# 2x_--_gegensprechanlage.net
KiCad netlist of a schematic drawn in EAGLE
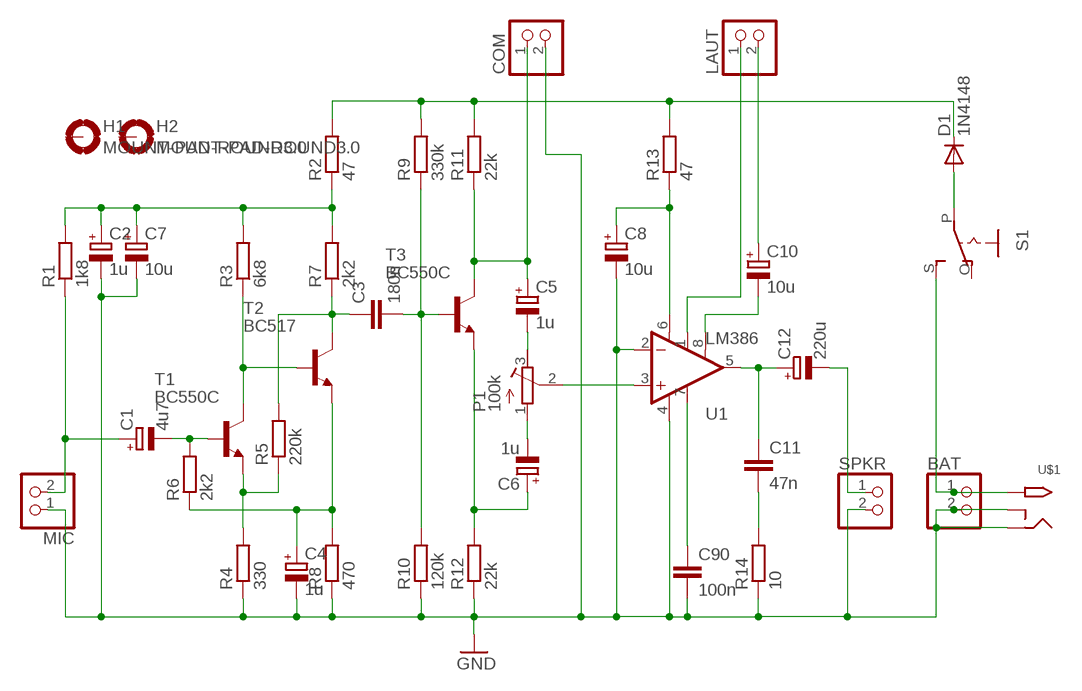
[diagram p0: schematic, sheet 1]

(export (version "E")
  (design (tool "Eeschema 10.0.6"))
  (components
    (comp (ref "BAT")
      (value "PINHD-1X2")
      (footprint "eagle-import:1X02")
      (libsource (lib "eagle-import") (part "PINHD-1X2"))
    )
    (comp (ref "C1")
      (value "4u7")
      (footprint "eagle-import:E2,5-6")
      (libsource (lib "eagle-import") (part "CPOL-EUE2.5-6"))
    )
    (comp (ref "C2")
      (value "1u")
      (footprint "eagle-import:E2,5-6")
      (libsource (lib "eagle-import") (part "CPOL-EUE2.5-6"))
    )
    (comp (ref "C3")
      (value "180n")
      (footprint "eagle-import:C025-025X050")
      (libsource (lib "eagle-import") (part "C-EU025-025X050"))
    )
    (comp (ref "C4")
      (value "1u")
      (footprint "eagle-import:E2,5-6")
      (libsource (lib "eagle-import") (part "CPOL-EUE2.5-6"))
    )
    (comp (ref "C5")
      (value "1u")
      (footprint "eagle-import:E2,5-6")
      (libsource (lib "eagle-import") (part "CPOL-EUE2.5-6"))
    )
    (comp (ref "C6")
      (value "1u")
      (footprint "eagle-import:E2,5-6")
      (libsource (lib "eagle-import") (part "CPOL-EUE2.5-6"))
    )
    (comp (ref "C7")
      (value "10u")
      (footprint "eagle-import:E2,5-6")
      (libsource (lib "eagle-import") (part "CPOL-EUE2.5-6"))
    )
    (comp (ref "C8")
      (value "10u")
      (footprint "eagle-import:E2,5-6")
      (libsource (lib "eagle-import") (part "CPOL-EUE2.5-6"))
    )
    (comp (ref "C10")
      (value "10u")
      (footprint "eagle-import:E2,5-6")
      (libsource (lib "eagle-import") (part "CPOL-EUE2.5-6"))
    )
    (comp (ref "C11")
      (value "47n")
      (footprint "eagle-import:C025-025X050")
      (libsource (lib "eagle-import") (part "C-EU025-025X050"))
    )
    (comp (ref "C12")
      (value "220u")
      (footprint "eagle-import:E2,5-6")
      (libsource (lib "eagle-import") (part "CPOL-EUE2.5-6"))
    )
    (comp (ref "C90")
      (value "100n")
      (footprint "eagle-import:C025-025X050")
      (libsource (lib "eagle-import") (part "C-EU025-025X050"))
    )
    (comp (ref "COM")
      (value "PINHD-1X2")
      (footprint "eagle-import:1X02")
      (libsource (lib "eagle-import") (part "PINHD-1X2"))
    )
    (comp (ref "D1")
      (value "1N4148")
      (footprint "eagle-import:D-7.5")
      (libsource (lib "eagle-import") (part "DIODE-D-7.5"))
    )
    (comp (ref "H1")
      (value "MOUNT-PAD-ROUND3.0")
      (footprint "eagle-import:3,0-PAD")
      (libsource (lib "eagle-import") (part "MOUNT-PAD-ROUND3.0"))
    )
    (comp (ref "H2")
      (value "MOUNT-PAD-ROUND3.0")
      (footprint "eagle-import:3,0-PAD")
      (libsource (lib "eagle-import") (part "MOUNT-PAD-ROUND3.0"))
    )
    (comp (ref "LAUT")
      (value "PINHD-1X2")
      (footprint "eagle-import:1X02")
      (libsource (lib "eagle-import") (part "PINHD-1X2"))
    )
    (comp (ref "MIC")
      (value "PINHD-1X2")
      (footprint "eagle-import:1X02")
      (libsource (lib "eagle-import") (part "PINHD-1X2"))
    )
    (comp (ref "P1")
      (value "100k")
      (footprint "eagle-import:RTRIM64P")
      (libsource (lib "eagle-import") (part "R-TRIMM64P"))
    )
    (comp (ref "R1")
      (value "1k8")
      (footprint "eagle-import:0204_7")
      (libsource (lib "eagle-import") (part "R-EU_0204/7"))
    )
    (comp (ref "R2")
      (value "47")
      (footprint "eagle-import:0204_7")
      (libsource (lib "eagle-import") (part "R-EU_0204/7"))
    )
    (comp (ref "R3")
      (value "6k8")
      (footprint "eagle-import:0204_7")
      (libsource (lib "eagle-import") (part "R-EU_0204/7"))
    )
    (comp (ref "R4")
      (value "330")
      (footprint "eagle-import:0204_7")
      (libsource (lib "eagle-import") (part "R-EU_0204/7"))
    )
    (comp (ref "R5")
      (value "220k")
      (footprint "eagle-import:0204_7")
      (libsource (lib "eagle-import") (part "R-EU_0204/7"))
    )
    (comp (ref "R6")
      (value "2k2")
      (footprint "eagle-import:0204_7")
      (libsource (lib "eagle-import") (part "R-EU_0204/7"))
    )
    (comp (ref "R7")
      (value "2k2")
      (footprint "eagle-import:0204_7")
      (libsource (lib "eagle-import") (part "R-EU_0204/7"))
    )
    (comp (ref "R8")
      (value "470")
      (footprint "eagle-import:0204_7")
      (libsource (lib "eagle-import") (part "R-EU_0204/7"))
    )
    (comp (ref "R9")
      (value "330k")
      (footprint "eagle-import:0204_7")
      (libsource (lib "eagle-import") (part "R-EU_0204/7"))
    )
    (comp (ref "R10")
      (value "120k")
      (footprint "eagle-import:0204_7")
      (libsource (lib "eagle-import") (part "R-EU_0204/7"))
    )
    (comp (ref "R11")
      (value "22k")
      (footprint "eagle-import:0204_7")
      (libsource (lib "eagle-import") (part "R-EU_0204/7"))
    )
    (comp (ref "R12")
      (value "22k")
      (footprint "eagle-import:0204_7")
      (libsource (lib "eagle-import") (part "R-EU_0204/7"))
    )
    (comp (ref "R13")
      (value "47")
      (footprint "eagle-import:0204_7")
      (libsource (lib "eagle-import") (part "R-EU_0204/7"))
    )
    (comp (ref "R14")
      (value "10")
      (footprint "eagle-import:0204_7")
      (libsource (lib "eagle-import") (part "R-EU_0204/7"))
    )
    (comp (ref "S1")
      (value "EG1218S")
      (footprint "eagle-import:EG1218")
      (libsource (lib "eagle-import") (part "EG1218S"))
    )
    (comp (ref "SPKR")
      (value "PINHD-1X2")
      (footprint "eagle-import:1X02")
      (libsource (lib "eagle-import") (part "PINHD-1X2"))
    )
    (comp (ref "T1")
      (value "BC550C")
      (footprint "eagle-import:TO92-CBE")
      (libsource (lib "eagle-import") (part "-NPN-TO92-CBEBC550"))
    )
    (comp (ref "T2")
      (value "BC517")
      (footprint "eagle-import:TO92-CBE")
      (libsource (lib "eagle-import") (part "-NPN-TO92-CBEBC550"))
    )
    (comp (ref "T3")
      (value "BC550C")
      (footprint "eagle-import:TO92-CBE")
      (libsource (lib "eagle-import") (part "-NPN-TO92-CBEBC550"))
    )
    (comp (ref "U$1")
      (value "2.1MMJACKTHM")
      (footprint "eagle-import:PJ-102A")
      (libsource (lib "eagle-import") (part "2.1MMJACKTHM"))
    )
    (comp (ref "U1")
      (value "LM386")
      (footprint "eagle-import:DIP08")
      (libsource (lib "eagle-import") (part "LM386"))
    )
  )
  (nets
    (net (code "1") (name "GND") (class "Default")
      (node (ref "BAT") (pin "2") (pinfunction "2_2") (pintype "passive"))
      (node (ref "C2") (pin "-") (pinfunction "-_-") (pintype "passive"))
      (node (ref "C4") (pin "-") (pinfunction "-_-") (pintype "passive"))
      (node (ref "C7") (pin "-") (pinfunction "-_-") (pintype "passive"))
      (node (ref "C8") (pin "-") (pinfunction "-_-") (pintype "passive"))
      (node (ref "C90") (pin "2") (pinfunction "2_2") (pintype "passive"))
      (node (ref "COM") (pin "2") (pinfunction "2_2") (pintype "passive"))
      (node (ref "MIC") (pin "1") (pinfunction "1_1") (pintype "passive"))
      (node (ref "R10") (pin "1") (pinfunction "1_1") (pintype "passive"))
      (node (ref "R12") (pin "1") (pinfunction "1_1") (pintype "passive"))
      (node (ref "R14") (pin "1") (pinfunction "1_1") (pintype "passive"))
      (node (ref "R4") (pin "1") (pinfunction "1_1") (pintype "passive"))
      (node (ref "R8") (pin "1") (pinfunction "1_1") (pintype "passive"))
      (node (ref "SPKR") (pin "2") (pinfunction "2_2") (pintype "passive"))
      (node (ref "U$1") (pin "RING") (pinfunction "RING_RING") (pintype "bidirectional"))
      (node (ref "U$1") (pin "RING_SW") (pinfunction "RING_SW_RING_SW") (pintype "bidirectional"))
      (node (ref "U1") (pin "2") (pinfunction "-IN_2") (pintype "input"))
      (node (ref "U1") (pin "4") (pinfunction "V-_4") (pintype "power_in"))
    )
    (net (code "2") (name "Net-(BAT-Pad1)") (class "Default")
      (node (ref "BAT") (pin "1") (pinfunction "1_1") (pintype "passive"))
      (node (ref "S1") (pin "S") (pinfunction "S_S") (pintype "passive"))
      (node (ref "U$1") (pin "TIP") (pinfunction "TIP_TIP") (pintype "bidirectional"))
    )
    (net (code "3") (name "Net-(C1-Pad+)") (class "Default")
      (node (ref "C1") (pin "+") (pinfunction "+_+") (pintype "passive"))
      (node (ref "MIC") (pin "2") (pinfunction "2_2") (pintype "passive"))
      (node (ref "R1") (pin "1") (pinfunction "1_1") (pintype "passive"))
    )
    (net (code "4") (name "Net-(C1-Pad-)") (class "Default")
      (node (ref "C1") (pin "-") (pinfunction "-_-") (pintype "passive"))
      (node (ref "R6") (pin "2") (pinfunction "2_2") (pintype "passive"))
      (node (ref "T1") (pin "B") (pinfunction "B_B") (pintype "passive"))
    )
    (net (code "5") (name "Net-(C2-Pad+)") (class "Default")
      (node (ref "C2") (pin "+") (pinfunction "+_+") (pintype "passive"))
      (node (ref "C7") (pin "+") (pinfunction "+_+") (pintype "passive"))
      (node (ref "R1") (pin "2") (pinfunction "2_2") (pintype "passive"))
      (node (ref "R2") (pin "1") (pinfunction "1_1") (pintype "passive"))
      (node (ref "R3") (pin "2") (pinfunction "2_2") (pintype "passive"))
      (node (ref "R7") (pin "2") (pinfunction "2_2") (pintype "passive"))
    )
    (net (code "6") (name "Net-(C3-Pad1)") (class "Default")
      (node (ref "C3") (pin "1") (pinfunction "1_1") (pintype "passive"))
      (node (ref "R5") (pin "2") (pinfunction "2_2") (pintype "passive"))
      (node (ref "R7") (pin "1") (pinfunction "1_1") (pintype "passive"))
      (node (ref "T2") (pin "C") (pinfunction "C_C") (pintype "passive"))
    )
    (net (code "7") (name "Net-(C3-Pad2)") (class "Default")
      (node (ref "C3") (pin "2") (pinfunction "2_2") (pintype "passive"))
      (node (ref "R10") (pin "2") (pinfunction "2_2") (pintype "passive"))
      (node (ref "R9") (pin "1") (pinfunction "1_1") (pintype "passive"))
      (node (ref "T3") (pin "B") (pinfunction "B_B") (pintype "passive"))
    )
    (net (code "8") (name "Net-(C4-Pad+)") (class "Default")
      (node (ref "C4") (pin "+") (pinfunction "+_+") (pintype "passive"))
      (node (ref "R6") (pin "1") (pinfunction "1_1") (pintype "passive"))
      (node (ref "R8") (pin "2") (pinfunction "2_2") (pintype "passive"))
      (node (ref "T2") (pin "E") (pinfunction "E_E") (pintype "passive"))
    )
    (net (code "9") (name "Net-(C5-Pad+)") (class "Default")
      (node (ref "C5") (pin "+") (pinfunction "+_+") (pintype "passive"))
      (node (ref "COM") (pin "1") (pinfunction "1_1") (pintype "passive"))
      (node (ref "R11") (pin "1") (pinfunction "1_1") (pintype "passive"))
      (node (ref "T3") (pin "C") (pinfunction "C_C") (pintype "passive"))
    )
    (net (code "10") (name "Net-(C6-Pad+)") (class "Default")
      (node (ref "C6") (pin "+") (pinfunction "+_+") (pintype "passive"))
      (node (ref "R12") (pin "2") (pinfunction "2_2") (pintype "passive"))
      (node (ref "T3") (pin "E") (pinfunction "E_E") (pintype "passive"))
    )
    (net (code "11") (name "Net-(C10-Pad+)") (class "Default")
      (node (ref "C10") (pin "+") (pinfunction "+_+") (pintype "passive"))
      (node (ref "LAUT") (pin "2") (pinfunction "2_2") (pintype "passive"))
    )
    (net (code "12") (name "Net-(C10-Pad-)") (class "Default")
      (node (ref "C10") (pin "-") (pinfunction "-_-") (pintype "passive"))
      (node (ref "U1") (pin "8") (pinfunction "GAIN_8") (pintype "bidirectional"))
    )
    (net (code "13") (name "Net-(C11-Pad2)") (class "Default")
      (node (ref "C11") (pin "2") (pinfunction "2_2") (pintype "passive"))
      (node (ref "R14") (pin "2") (pinfunction "2_2") (pintype "passive"))
    )
    (net (code "14") (name "Net-(C12-Pad-)") (class "Default")
      (node (ref "C12") (pin "-") (pinfunction "-_-") (pintype "passive"))
      (node (ref "SPKR") (pin "1") (pinfunction "1_1") (pintype "passive"))
    )
    (net (code "15") (name "Net-(D1-PadA)") (class "Default")
      (node (ref "D1") (pin "A") (pinfunction "A_A") (pintype "passive"))
      (node (ref "S1") (pin "P") (pinfunction "P_P") (pintype "passive"))
    )
    (net (code "16") (name "Net-(D1-PadC)") (class "Default")
      (node (ref "D1") (pin "C") (pinfunction "C_C") (pintype "passive"))
      (node (ref "R11") (pin "2") (pinfunction "2_2") (pintype "passive"))
      (node (ref "R13") (pin "2") (pinfunction "2_2") (pintype "passive"))
      (node (ref "R2") (pin "2") (pinfunction "2_2") (pintype "passive"))
      (node (ref "R9") (pin "2") (pinfunction "2_2") (pintype "passive"))
    )
    (net (code "17") (name "Net-(LAUT-Pad1)") (class "Default")
      (node (ref "LAUT") (pin "1") (pinfunction "1_1") (pintype "passive"))
      (node (ref "U1") (pin "1") (pinfunction "GAIN_1") (pintype "bidirectional"))
    )
    (net (code "18") (name "Net-(P1-A)") (class "Default")
      (node (ref "C6") (pin "-") (pinfunction "-_-") (pintype "passive"))
      (node (ref "P1") (pin "1") (pinfunction "A_1") (pintype "passive"))
    )
    (net (code "19") (name "Net-(P1-E)") (class "Default")
      (node (ref "C5") (pin "-") (pinfunction "-_-") (pintype "passive"))
      (node (ref "P1") (pin "3") (pinfunction "E_3") (pintype "passive"))
    )
    (net (code "20") (name "Net-(P1-S)") (class "Default")
      (node (ref "P1") (pin "2") (pinfunction "S_2") (pintype "passive"))
      (node (ref "U1") (pin "3") (pinfunction "+IN_3") (pintype "input"))
    )
    (net (code "21") (name "Net-(R3-Pad1)") (class "Default")
      (node (ref "R3") (pin "1") (pinfunction "1_1") (pintype "passive"))
      (node (ref "T1") (pin "C") (pinfunction "C_C") (pintype "passive"))
      (node (ref "T2") (pin "B") (pinfunction "B_B") (pintype "passive"))
    )
    (net (code "22") (name "Net-(R4-Pad2)") (class "Default")
      (node (ref "R4") (pin "2") (pinfunction "2_2") (pintype "passive"))
      (node (ref "R5") (pin "1") (pinfunction "1_1") (pintype "passive"))
      (node (ref "T1") (pin "E") (pinfunction "E_E") (pintype "passive"))
    )
    (net (code "23") (name "Net-(U1-BP)") (class "Default")
      (node (ref "C90") (pin "1") (pinfunction "1_1") (pintype "passive"))
      (node (ref "U1") (pin "7") (pinfunction "BP_7") (pintype "bidirectional"))
    )
    (net (code "24") (name "Net-(U1-OUT)") (class "Default")
      (node (ref "C11") (pin "1") (pinfunction "1_1") (pintype "passive"))
      (node (ref "C12") (pin "+") (pinfunction "+_+") (pintype "passive"))
      (node (ref "U1") (pin "5") (pinfunction "OUT_5") (pintype "output"))
    )
    (net (code "25") (name "Net-(U1-V+)") (class "Default")
      (node (ref "C8") (pin "+") (pinfunction "+_+") (pintype "passive"))
      (node (ref "R13") (pin "1") (pinfunction "1_1") (pintype "passive"))
      (node (ref "U1") (pin "6") (pinfunction "V+_6") (pintype "power_in"))
    )
    (net (code "26") (name "unconnected-(H1-MOUNT-PadB3,0)") (class "Default")
      (node (ref "H1") (pin "B3,0") (pinfunction "MOUNT_B3,0") (pintype "passive"))
    )
    (net (code "27") (name "unconnected-(H2-MOUNT-PadB3,0)") (class "Default")
      (node (ref "H2") (pin "B3,0") (pinfunction "MOUNT_B3,0") (pintype "passive"))
    )
    (net (code "28") (name "unconnected-(S1-PadO)") (class "Default")
      (node (ref "S1") (pin "O") (pinfunction "O_O") (pintype "passive"))
    )
  )
)
